# small_line.net
KiCad netlist of a schematic drawn in EAGLE
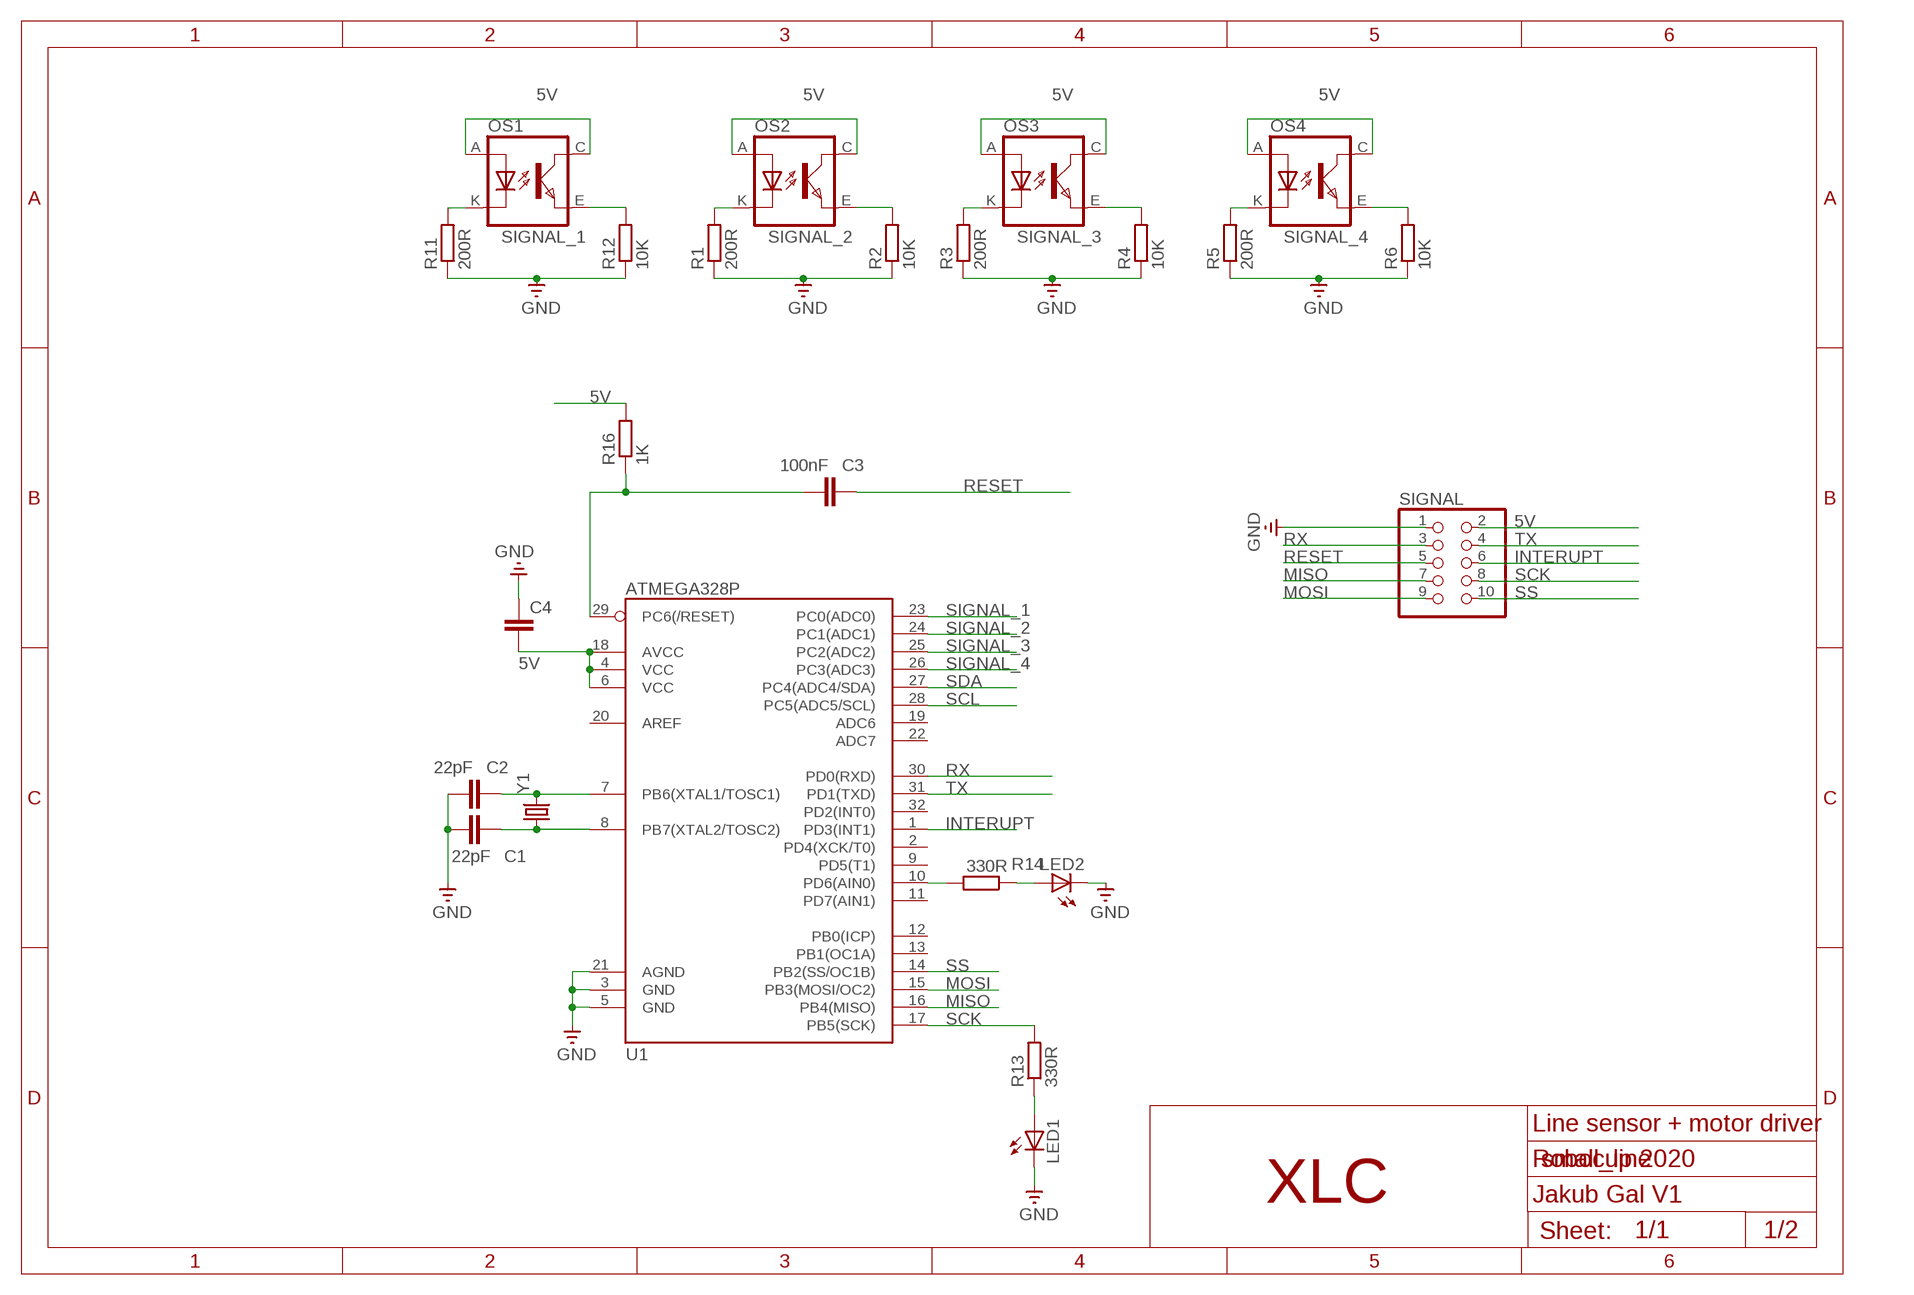
[diagram p0: schematic, sheet 1]

(export (version "E")
  (design (tool "Eeschema 10.0.6"))
  (components
    (comp (ref "C1")
      (value "22pF")
      (footprint "eagle-import:C0603")
      (libsource (lib "eagle-import") (part "C-EUC0603"))
    )
    (comp (ref "C2")
      (value "22pF")
      (footprint "eagle-import:C0603")
      (libsource (lib "eagle-import") (part "C-EUC0603"))
    )
    (comp (ref "C3")
      (value "100nF")
      (footprint "eagle-import:C0603")
      (libsource (lib "eagle-import") (part "C-EUC0603"))
    )
    (comp (ref "C4")
      (value "C-EUC0603")
      (footprint "eagle-import:C0603")
      (libsource (lib "eagle-import") (part "rcl_334_C-EUC0603"))
    )
    (comp (ref "LED1")
      (value "LEDCHIPLED_0603")
      (footprint "eagle-import:CHIPLED_0603")
      (libsource (lib "eagle-import") (part "LEDCHIPLED_0603"))
    )
    (comp (ref "LED2")
      (value "LEDCHIPLED_0603")
      (footprint "eagle-import:CHIPLED_0603")
      (libsource (lib "eagle-import") (part "LEDCHIPLED_0603"))
    )
    (comp (ref "OS1")
      (value "TCRT5000")
      (footprint "eagle-import:TCRT5000")
      (libsource (lib "eagle-import") (part "TCRT5000"))
    )
    (comp (ref "OS2")
      (value "TCRT5000")
      (footprint "eagle-import:TCRT5000")
      (libsource (lib "eagle-import") (part "TCRT5000"))
    )
    (comp (ref "OS3")
      (value "TCRT5000")
      (footprint "eagle-import:TCRT5000")
      (libsource (lib "eagle-import") (part "TCRT5000"))
    )
    (comp (ref "OS4")
      (value "TCRT5000")
      (footprint "eagle-import:TCRT5000")
      (libsource (lib "eagle-import") (part "TCRT5000"))
    )
    (comp (ref "R1")
      (value "200R")
      (footprint "eagle-import:R0603")
      (libsource (lib "eagle-import") (part "R-EU_R0603"))
    )
    (comp (ref "R2")
      (value "10K")
      (footprint "eagle-import:R0603")
      (libsource (lib "eagle-import") (part "R-EU_R0603"))
    )
    (comp (ref "R3")
      (value "200R")
      (footprint "eagle-import:R0603")
      (libsource (lib "eagle-import") (part "R-EU_R0603"))
    )
    (comp (ref "R4")
      (value "10K")
      (footprint "eagle-import:R0603")
      (libsource (lib "eagle-import") (part "R-EU_R0603"))
    )
    (comp (ref "R5")
      (value "200R")
      (footprint "eagle-import:R0603")
      (libsource (lib "eagle-import") (part "R-EU_R0603"))
    )
    (comp (ref "R6")
      (value "10K")
      (footprint "eagle-import:R0603")
      (libsource (lib "eagle-import") (part "R-EU_R0603"))
    )
    (comp (ref "R11")
      (value "200R")
      (footprint "eagle-import:R0603")
      (libsource (lib "eagle-import") (part "R-EU_R0603"))
    )
    (comp (ref "R12")
      (value "10K")
      (footprint "eagle-import:R0603")
      (libsource (lib "eagle-import") (part "R-EU_R0603"))
    )
    (comp (ref "R13")
      (value "330R")
      (footprint "eagle-import:R0603")
      (libsource (lib "eagle-import") (part "R-EU_R0603"))
    )
    (comp (ref "R14")
      (value "330R")
      (footprint "eagle-import:R0603")
      (libsource (lib "eagle-import") (part "R-EU_R0603"))
    )
    (comp (ref "R16")
      (value "1K")
      (footprint "eagle-import:R0603")
      (libsource (lib "eagle-import") (part "R-EU_R0603"))
    )
    (comp (ref "SIGNAL")
      (value "PINHD-2X5")
      (footprint "eagle-import:2X05")
      (libsource (lib "eagle-import") (part "PINHD-2X5"))
    )
    (comp (ref "U1")
      (value "ATMEGA328P")
      (footprint "eagle-import:TQFP32-08")
      (libsource (lib "eagle-import") (part "ATMEGA328_SMT"))
    )
    (comp (ref "Y1")
      (value "CRYSTALHC49US")
      (footprint "eagle-import:HC49US")
      (libsource (lib "eagle-import") (part "CRYSTALHC49US"))
    )
  )
  (nets
    (net (code "1") (name "/5V") (class "Default")
      (node (ref "C4") (pin "2") (pinfunction "2_2") (pintype "passive"))
      (node (ref "OS1") (pin "A") (pinfunction "ANODE_A") (pintype "passive"))
      (node (ref "OS1") (pin "C") (pinfunction "COLLECTOR_C") (pintype "passive"))
      (node (ref "OS2") (pin "A") (pinfunction "ANODE_A") (pintype "passive"))
      (node (ref "OS2") (pin "C") (pinfunction "COLLECTOR_C") (pintype "passive"))
      (node (ref "OS3") (pin "A") (pinfunction "ANODE_A") (pintype "passive"))
      (node (ref "OS3") (pin "C") (pinfunction "COLLECTOR_C") (pintype "passive"))
      (node (ref "OS4") (pin "A") (pinfunction "ANODE_A") (pintype "passive"))
      (node (ref "OS4") (pin "C") (pinfunction "COLLECTOR_C") (pintype "passive"))
      (node (ref "R16") (pin "2") (pinfunction "2_2") (pintype "passive"))
      (node (ref "SIGNAL") (pin "2") (pinfunction "2_2") (pintype "passive"))
      (node (ref "U1") (pin "18") (pinfunction "AVCC_18") (pintype "bidirectional"))
      (node (ref "U1") (pin "4") (pinfunction "VCC_4") (pintype "bidirectional"))
      (node (ref "U1") (pin "6") (pinfunction "VCC_6") (pintype "bidirectional"))
    )
    (net (code "2") (name "/INTERUPT") (class "Default")
      (node (ref "SIGNAL") (pin "6") (pinfunction "6_6") (pintype "passive"))
      (node (ref "U1") (pin "1") (pinfunction "PD3(INT1)_1") (pintype "bidirectional"))
    )
    (net (code "3") (name "/MISO") (class "Default")
      (node (ref "SIGNAL") (pin "7") (pinfunction "7_7") (pintype "passive"))
      (node (ref "U1") (pin "16") (pinfunction "PB4(MISO)_16") (pintype "bidirectional"))
    )
    (net (code "4") (name "/MOSI") (class "Default")
      (node (ref "SIGNAL") (pin "9") (pinfunction "9_9") (pintype "passive"))
      (node (ref "U1") (pin "15") (pinfunction "PB3(MOSI/OC2)_15") (pintype "bidirectional"))
    )
    (net (code "5") (name "/RESET") (class "Default")
      (node (ref "C3") (pin "2") (pinfunction "2_2") (pintype "passive"))
      (node (ref "SIGNAL") (pin "5") (pinfunction "5_5") (pintype "passive"))
    )
    (net (code "6") (name "/RX") (class "Default")
      (node (ref "SIGNAL") (pin "3") (pinfunction "3_3") (pintype "passive"))
      (node (ref "U1") (pin "30") (pinfunction "PD0(RXD)_30") (pintype "bidirectional"))
    )
    (net (code "7") (name "/SCK") (class "Default")
      (node (ref "R13") (pin "2") (pinfunction "2_2") (pintype "passive"))
      (node (ref "SIGNAL") (pin "8") (pinfunction "8_8") (pintype "passive"))
      (node (ref "U1") (pin "17") (pinfunction "PB5(SCK)_17") (pintype "bidirectional"))
    )
    (net (code "8") (name "/SCL") (class "Default")
      (node (ref "U1") (pin "28") (pinfunction "PC5(ADC5/SCL)_28") (pintype "bidirectional"))
    )
    (net (code "9") (name "/SDA") (class "Default")
      (node (ref "U1") (pin "27") (pinfunction "PC4(ADC4/SDA)_27") (pintype "bidirectional"))
    )
    (net (code "10") (name "/SIGNAL_1") (class "Default")
      (node (ref "OS1") (pin "E") (pinfunction "EMITTER_E") (pintype "passive"))
      (node (ref "R12") (pin "2") (pinfunction "2_2") (pintype "passive"))
      (node (ref "U1") (pin "23") (pinfunction "PC0(ADC0)_23") (pintype "bidirectional"))
    )
    (net (code "11") (name "/SIGNAL_2") (class "Default")
      (node (ref "OS2") (pin "E") (pinfunction "EMITTER_E") (pintype "passive"))
      (node (ref "R2") (pin "2") (pinfunction "2_2") (pintype "passive"))
      (node (ref "U1") (pin "24") (pinfunction "PC1(ADC1)_24") (pintype "bidirectional"))
    )
    (net (code "12") (name "/SIGNAL_3") (class "Default")
      (node (ref "OS3") (pin "E") (pinfunction "EMITTER_E") (pintype "passive"))
      (node (ref "R4") (pin "2") (pinfunction "2_2") (pintype "passive"))
      (node (ref "U1") (pin "25") (pinfunction "PC2(ADC2)_25") (pintype "bidirectional"))
    )
    (net (code "13") (name "/SIGNAL_4") (class "Default")
      (node (ref "OS4") (pin "E") (pinfunction "EMITTER_E") (pintype "passive"))
      (node (ref "R6") (pin "2") (pinfunction "2_2") (pintype "passive"))
      (node (ref "U1") (pin "26") (pinfunction "PC3(ADC3)_26") (pintype "bidirectional"))
    )
    (net (code "14") (name "/SS") (class "Default")
      (node (ref "SIGNAL") (pin "10") (pinfunction "10_10") (pintype "passive"))
      (node (ref "U1") (pin "14") (pinfunction "PB2(SS/OC1B)_14") (pintype "bidirectional"))
    )
    (net (code "15") (name "/TX") (class "Default")
      (node (ref "SIGNAL") (pin "4") (pinfunction "4_4") (pintype "passive"))
      (node (ref "U1") (pin "31") (pinfunction "PD1(TXD)_31") (pintype "bidirectional"))
    )
    (net (code "16") (name "GND") (class "Default")
      (node (ref "C1") (pin "1") (pinfunction "1_1") (pintype "passive"))
      (node (ref "C2") (pin "1") (pinfunction "1_1") (pintype "passive"))
      (node (ref "C4") (pin "1") (pinfunction "1_1") (pintype "passive"))
      (node (ref "LED1") (pin "C") (pinfunction "C_C") (pintype "passive"))
      (node (ref "LED2") (pin "C") (pinfunction "C_C") (pintype "passive"))
      (node (ref "R1") (pin "1") (pinfunction "1_1") (pintype "passive"))
      (node (ref "R11") (pin "1") (pinfunction "1_1") (pintype "passive"))
      (node (ref "R12") (pin "1") (pinfunction "1_1") (pintype "passive"))
      (node (ref "R2") (pin "1") (pinfunction "1_1") (pintype "passive"))
      (node (ref "R3") (pin "1") (pinfunction "1_1") (pintype "passive"))
      (node (ref "R4") (pin "1") (pinfunction "1_1") (pintype "passive"))
      (node (ref "R5") (pin "1") (pinfunction "1_1") (pintype "passive"))
      (node (ref "R6") (pin "1") (pinfunction "1_1") (pintype "passive"))
      (node (ref "SIGNAL") (pin "1") (pinfunction "1_1") (pintype "passive"))
      (node (ref "U1") (pin "21") (pinfunction "AGND_21") (pintype "bidirectional"))
      (node (ref "U1") (pin "3") (pinfunction "GND_3") (pintype "bidirectional"))
      (node (ref "U1") (pin "5") (pinfunction "GND_5") (pintype "bidirectional"))
    )
    (net (code "17") (name "Net-(LED1-PadA)") (class "Default")
      (node (ref "LED1") (pin "A") (pinfunction "A_A") (pintype "passive"))
      (node (ref "R13") (pin "1") (pinfunction "1_1") (pintype "passive"))
    )
    (net (code "18") (name "Net-(LED2-PadA)") (class "Default")
      (node (ref "LED2") (pin "A") (pinfunction "A_A") (pintype "passive"))
      (node (ref "R14") (pin "1") (pinfunction "1_1") (pintype "passive"))
    )
    (net (code "19") (name "Net-(OS1-CATHODE)") (class "Default")
      (node (ref "OS1") (pin "K") (pinfunction "CATHODE_K") (pintype "passive"))
      (node (ref "R11") (pin "2") (pinfunction "2_2") (pintype "passive"))
    )
    (net (code "20") (name "Net-(OS2-CATHODE)") (class "Default")
      (node (ref "OS2") (pin "K") (pinfunction "CATHODE_K") (pintype "passive"))
      (node (ref "R1") (pin "2") (pinfunction "2_2") (pintype "passive"))
    )
    (net (code "21") (name "Net-(OS3-CATHODE)") (class "Default")
      (node (ref "OS3") (pin "K") (pinfunction "CATHODE_K") (pintype "passive"))
      (node (ref "R3") (pin "2") (pinfunction "2_2") (pintype "passive"))
    )
    (net (code "22") (name "Net-(OS4-CATHODE)") (class "Default")
      (node (ref "OS4") (pin "K") (pinfunction "CATHODE_K") (pintype "passive"))
      (node (ref "R5") (pin "2") (pinfunction "2_2") (pintype "passive"))
    )
    (net (code "23") (name "Net-(U1-PB6(XTAL1{slash}TOSC1))") (class "Default")
      (node (ref "C2") (pin "2") (pinfunction "2_2") (pintype "passive"))
      (node (ref "U1") (pin "7") (pinfunction "PB6(XTAL1/TOSC1)_7") (pintype "bidirectional"))
      (node (ref "Y1") (pin "2") (pinfunction "2_2") (pintype "passive"))
    )
    (net (code "24") (name "Net-(U1-PB7(XTAL2{slash}TOSC2))") (class "Default")
      (node (ref "C1") (pin "2") (pinfunction "2_2") (pintype "passive"))
      (node (ref "U1") (pin "8") (pinfunction "PB7(XTAL2/TOSC2)_8") (pintype "bidirectional"))
      (node (ref "Y1") (pin "1") (pinfunction "1_1") (pintype "passive"))
    )
    (net (code "25") (name "Net-(U1-PC6({slash}RESET))") (class "Default")
      (node (ref "C3") (pin "1") (pinfunction "1_1") (pintype "passive"))
      (node (ref "R16") (pin "1") (pinfunction "1_1") (pintype "passive"))
      (node (ref "U1") (pin "29") (pinfunction "PC6(/RESET)_29") (pintype "bidirectional"))
    )
    (net (code "26") (name "Net-(U1-PD6(AIN0))") (class "Default")
      (node (ref "R14") (pin "2") (pinfunction "2_2") (pintype "passive"))
      (node (ref "U1") (pin "10") (pinfunction "PD6(AIN0)_10") (pintype "bidirectional"))
    )
    (net (code "27") (name "unconnected-(U1-ADC6-Pad19)") (class "Default")
      (node (ref "U1") (pin "19") (pinfunction "ADC6_19") (pintype "bidirectional"))
    )
    (net (code "28") (name "unconnected-(U1-ADC7-Pad22)") (class "Default")
      (node (ref "U1") (pin "22") (pinfunction "ADC7_22") (pintype "bidirectional"))
    )
    (net (code "29") (name "unconnected-(U1-AREF-Pad20)") (class "Default")
      (node (ref "U1") (pin "20") (pinfunction "AREF_20") (pintype "bidirectional"))
    )
    (net (code "30") (name "unconnected-(U1-PB0(ICP)-Pad12)") (class "Default")
      (node (ref "U1") (pin "12") (pinfunction "PB0(ICP)_12") (pintype "bidirectional"))
    )
    (net (code "31") (name "unconnected-(U1-PB1(OC1A)-Pad13)") (class "Default")
      (node (ref "U1") (pin "13") (pinfunction "PB1(OC1A)_13") (pintype "bidirectional"))
    )
    (net (code "32") (name "unconnected-(U1-PD2(INT0)-Pad32)") (class "Default")
      (node (ref "U1") (pin "32") (pinfunction "PD2(INT0)_32") (pintype "bidirectional"))
    )
    (net (code "33") (name "unconnected-(U1-PD4(XCK{slash}T0)-Pad2)") (class "Default")
      (node (ref "U1") (pin "2") (pinfunction "PD4(XCK/T0)_2") (pintype "bidirectional"))
    )
    (net (code "34") (name "unconnected-(U1-PD5(T1)-Pad9)") (class "Default")
      (node (ref "U1") (pin "9") (pinfunction "PD5(T1)_9") (pintype "bidirectional"))
    )
    (net (code "35") (name "unconnected-(U1-PD7(AIN1)-Pad11)") (class "Default")
      (node (ref "U1") (pin "11") (pinfunction "PD7(AIN1)_11") (pintype "bidirectional"))
    )
  )
)
